# LPmini-Prototype_1_4b.net
KiCad netlist of a schematic drawn in EAGLE
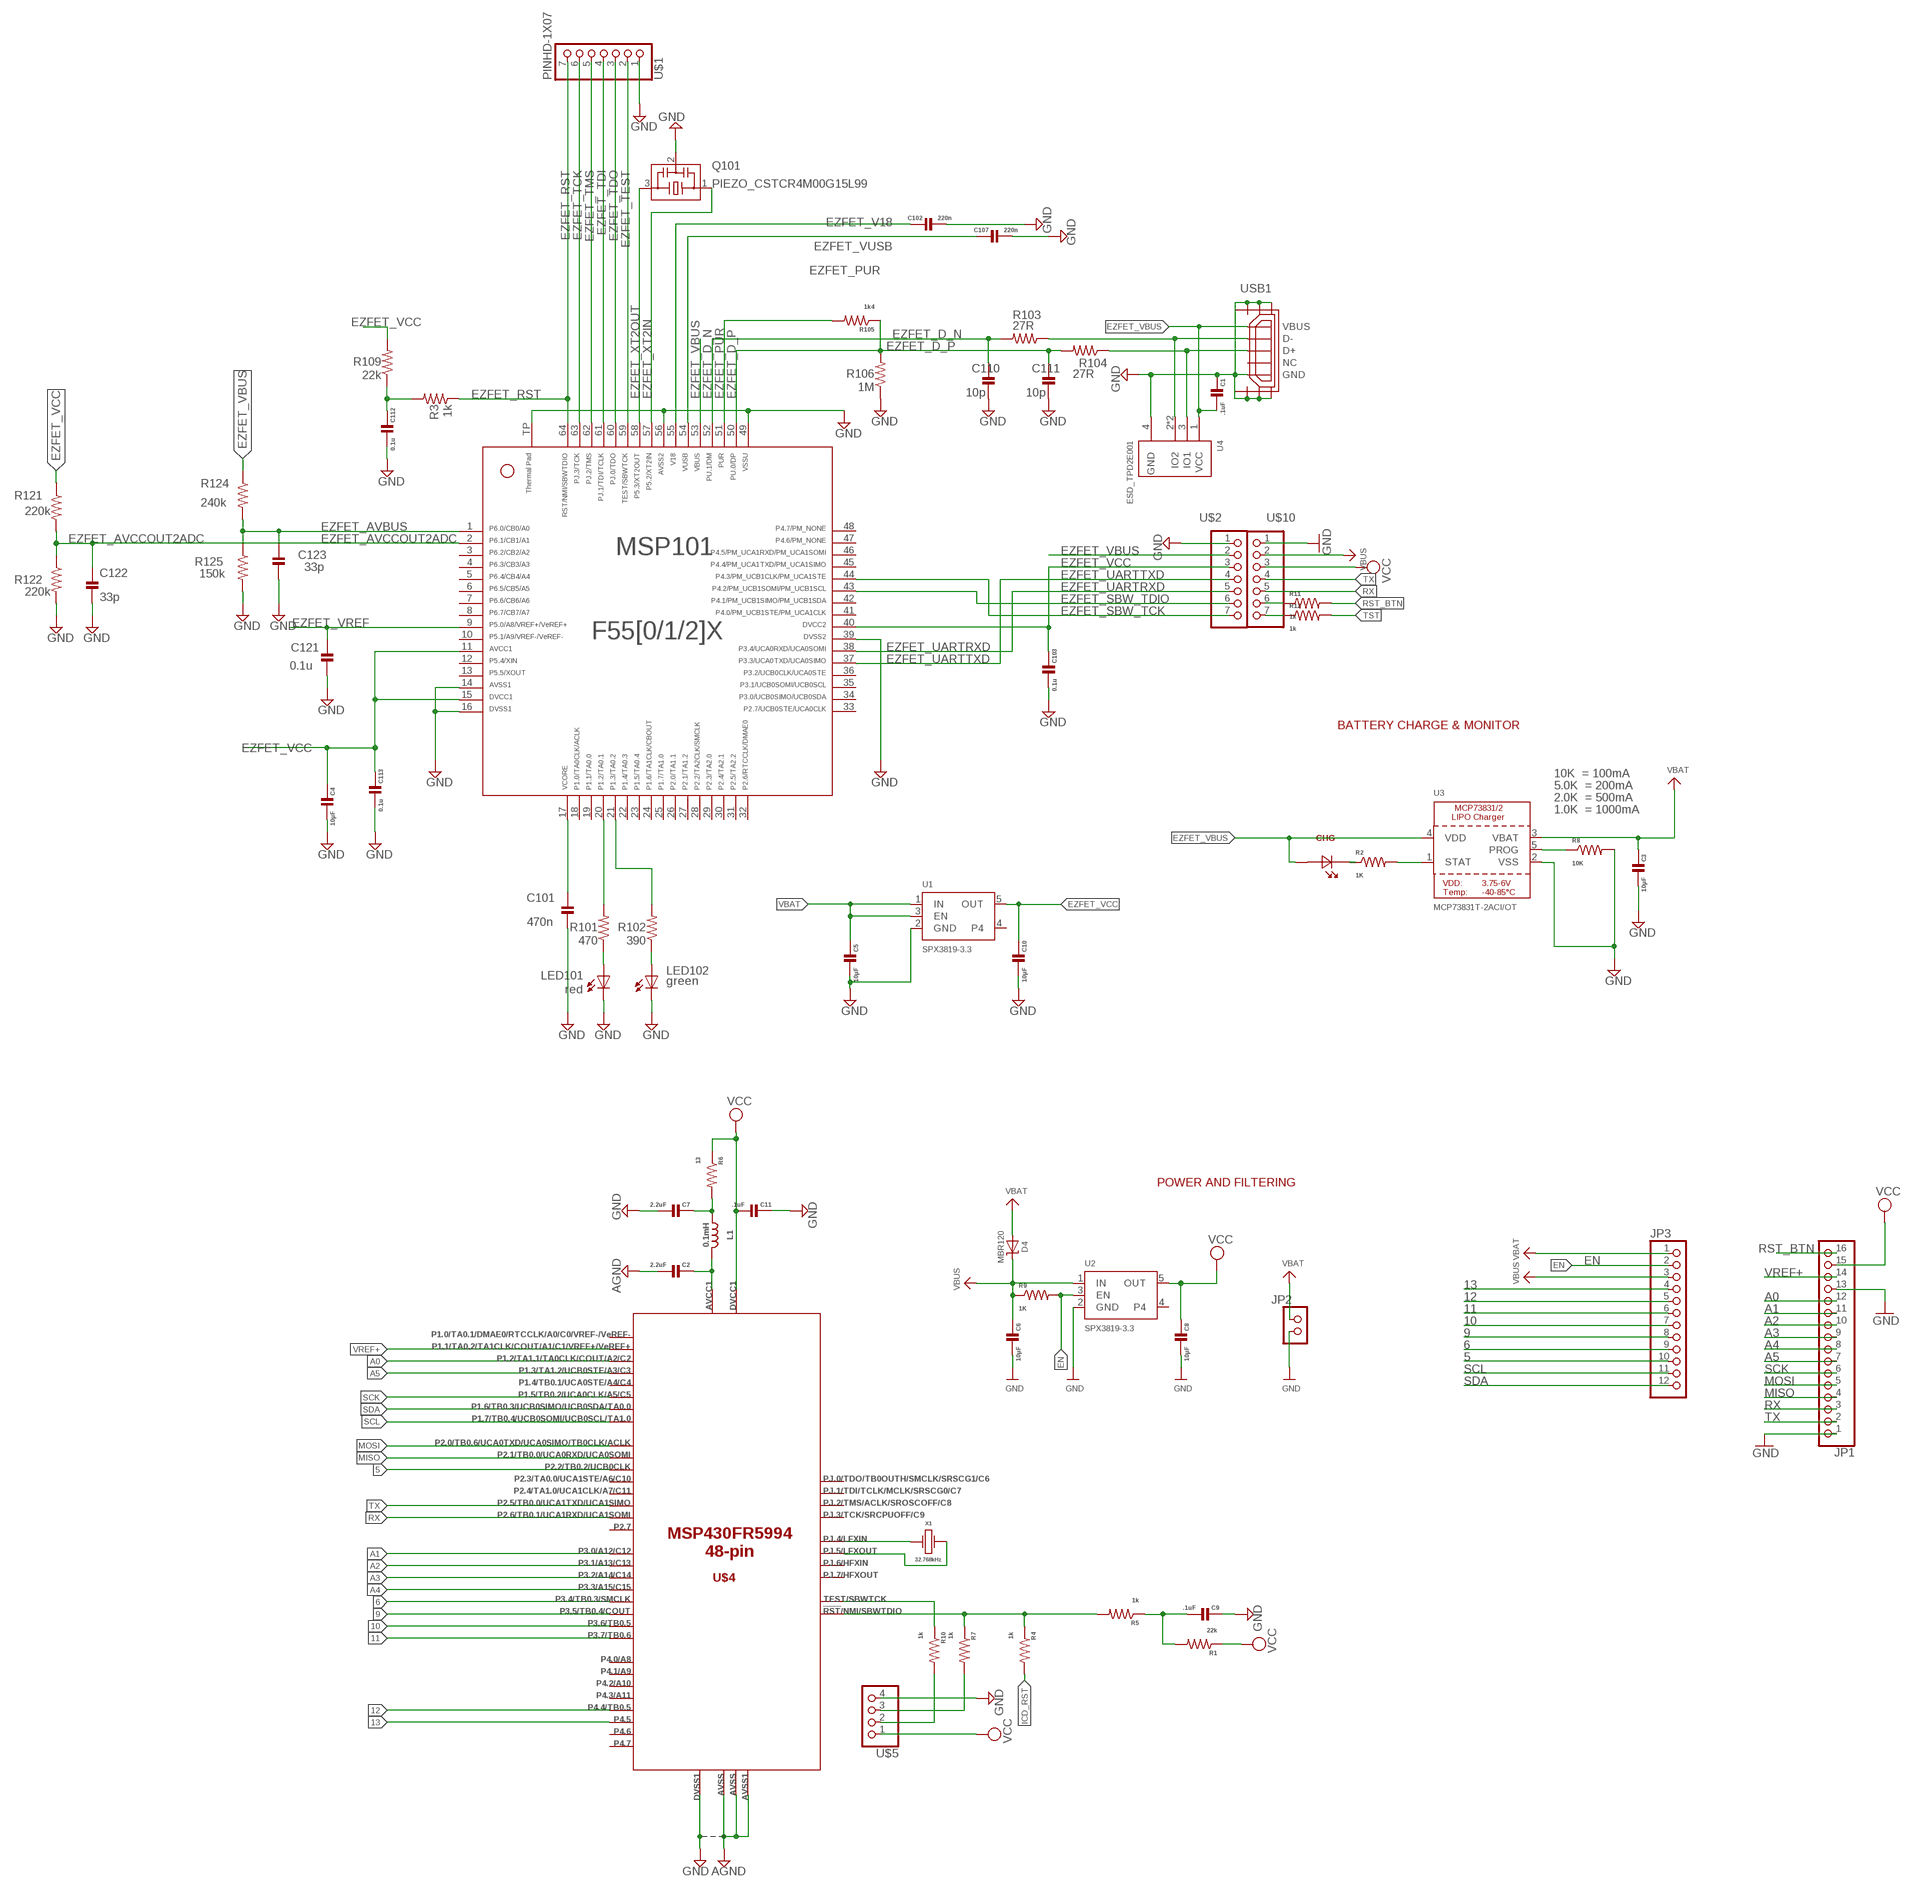
[diagram p0: schematic, sheet 1]

(export (version "E")
  (design (tool "Eeschema 10.0.6"))
  (components
    (comp (ref "C1")
      (value ".1uF")
      (footprint "eagle-import:C0402")
      (libsource (lib "eagle-import") (part "C-EUC0402"))
    )
    (comp (ref "C2")
      (value "2.2uF")
      (footprint "eagle-import:C0603")
      (libsource (lib "eagle-import") (part "C-EUC0603"))
    )
    (comp (ref "C3")
      (value "10µF")
      (footprint "eagle-import:C0603")
      (libsource (lib "eagle-import") (part "C-EUC0603"))
    )
    (comp (ref "C4")
      (value "10µF")
      (footprint "eagle-import:C0603")
      (libsource (lib "eagle-import") (part "C-EUC0603"))
    )
    (comp (ref "C5")
      (value "10µF")
      (footprint "eagle-import:C0603")
      (libsource (lib "eagle-import") (part "C-EUC0603"))
    )
    (comp (ref "C6")
      (value "10µF")
      (footprint "eagle-import:C0603")
      (libsource (lib "eagle-import") (part "C-EUC0603"))
    )
    (comp (ref "C7")
      (value "2.2uF")
      (footprint "eagle-import:C0603")
      (libsource (lib "eagle-import") (part "C-EUC0603"))
    )
    (comp (ref "C8")
      (value "10µF")
      (footprint "eagle-import:C0603")
      (libsource (lib "eagle-import") (part "C-EUC0603"))
    )
    (comp (ref "C9")
      (value ".1uF")
      (footprint "eagle-import:C0402")
      (libsource (lib "eagle-import") (part "C-EUC0402"))
    )
    (comp (ref "C10")
      (value "10µF")
      (footprint "eagle-import:C0603")
      (libsource (lib "eagle-import") (part "C-EUC0603"))
    )
    (comp (ref "C11")
      (value ".1uF")
      (footprint "eagle-import:C0402")
      (libsource (lib "eagle-import") (part "C-EUC0402"))
    )
    (comp (ref "C101")
      (value "470n")
      (footprint "eagle-import:C0402")
      (libsource (lib "eagle-import") (part "C-EUC0402"))
    )
    (comp (ref "C102")
      (value "220n")
      (footprint "eagle-import:C0402")
      (libsource (lib "eagle-import") (part "C-EUC0402"))
    )
    (comp (ref "C103")
      (value "0.1u")
      (footprint "eagle-import:C0402")
      (libsource (lib "eagle-import") (part "C-EUC0402"))
    )
    (comp (ref "C107")
      (value "220n")
      (footprint "eagle-import:C0402")
      (libsource (lib "eagle-import") (part "C-EUC0402"))
    )
    (comp (ref "C110")
      (value "10p")
      (footprint "eagle-import:C0402")
      (libsource (lib "eagle-import") (part "C-EUC0402"))
    )
    (comp (ref "C111")
      (value "10p")
      (footprint "eagle-import:C0402")
      (libsource (lib "eagle-import") (part "C-EUC0402"))
    )
    (comp (ref "C112")
      (value "0.1u")
      (footprint "eagle-import:C0402")
      (libsource (lib "eagle-import") (part "C-EUC0402"))
    )
    (comp (ref "C113")
      (value "0.1u")
      (footprint "eagle-import:C0402")
      (libsource (lib "eagle-import") (part "C-EUC0402"))
    )
    (comp (ref "C121")
      (value "0.1u")
      (footprint "eagle-import:C0402")
      (libsource (lib "eagle-import") (part "C-EUC0402"))
    )
    (comp (ref "C122")
      (value "33p")
      (footprint "eagle-import:C0402")
      (libsource (lib "eagle-import") (part "C-EUC0402"))
    )
    (comp (ref "C123")
      (value "33p")
      (footprint "eagle-import:C0402")
      (libsource (lib "eagle-import") (part "C-EUC0402"))
    )
    (comp (ref "CHG")
      (value "ORANGE")
      (footprint "eagle-import:LED_0603")
      (libsource (lib "eagle-import") (part "LED0603"))
    )
    (comp (ref "D4")
      (value "MBR120")
      (footprint "eagle-import:SOD-123")
      (libsource (lib "eagle-import") (part "DIODE-SCHOTTKYSOD-123"))
    )
    (comp (ref "JP1")
      (value "HEADER-1X16ROUND")
      (footprint "eagle-import:1X16_ROUND")
      (libsource (lib "eagle-import") (part "HEADER-1X16ROUND"))
    )
    (comp (ref "JP2")
      (value "0_JOSEPH_PINHD-1X2END")
      (footprint "eagle-import:0_JOSEPH_1X02-END")
      (libsource (lib "eagle-import") (part "0_JOSEPH_PINHD-1X2END"))
    )
    (comp (ref "JP3")
      (value "HEADER-1X12")
      (footprint "eagle-import:1X12_ROUND")
      (libsource (lib "eagle-import") (part "HEADER-1X12"))
    )
    (comp (ref "L1")
      (value "0.1mH")
      (footprint "eagle-import:RCL_R0805")
      (libsource (lib "eagle-import") (part "SMD_INDUCT0805"))
    )
    (comp (ref "LED101")
      (value "red")
      (footprint "eagle-import:CHIP-LED0603")
      (libsource (lib "eagle-import") (part "LEDCHIP-LED0603"))
    )
    (comp (ref "LED102")
      (value "green")
      (footprint "eagle-import:CHIP-LED0603")
      (libsource (lib "eagle-import") (part "LEDCHIP-LED0603"))
    )
    (comp (ref "MSP101")
      (value "MSP430F5528IRGC")
      (footprint "eagle-import:RGC64")
      (libsource (lib "eagle-import") (part "F55[0/1/2]X---RGC64"))
    )
    (comp (ref "Q101")
      (value "PIEZO_CSTCR4M00G15L99")
      (footprint "eagle-import:MURATA-FILTER_CSTCR")
      (fields (field (name "MPN") "CSTCR6M00G53-R0"))
      (libsource (lib "eagle-import") (part "MURATA-FILTER_CSTCR6M00G53Z"))
    )
    (comp (ref "R1")
      (value "22k")
      (footprint "eagle-import:R0402")
      (libsource (lib "eagle-import") (part "R-US_R0402"))
    )
    (comp (ref "R2")
      (value "1K")
      (footprint "eagle-import:R0402")
      (libsource (lib "eagle-import") (part "R-US_R0402"))
    )
    (comp (ref "R3")
      (value "1k")
      (footprint "eagle-import:R0402")
      (libsource (lib "eagle-import") (part "R-US_R0402"))
    )
    (comp (ref "R4")
      (value "1k")
      (footprint "eagle-import:R0402")
      (libsource (lib "eagle-import") (part "R-US_R0402"))
    )
    (comp (ref "R5")
      (value "1k")
      (footprint "eagle-import:R0402")
      (libsource (lib "eagle-import") (part "R-US_R0402"))
    )
    (comp (ref "R6")
      (value "13")
      (footprint "eagle-import:R0402")
      (libsource (lib "eagle-import") (part "R-US_R0402"))
    )
    (comp (ref "R7")
      (value "1k")
      (footprint "eagle-import:R0402")
      (libsource (lib "eagle-import") (part "R-US_R0402"))
    )
    (comp (ref "R8")
      (value "10K")
      (footprint "eagle-import:R0402")
      (libsource (lib "eagle-import") (part "R-US_R0402"))
    )
    (comp (ref "R9")
      (value "1K")
      (footprint "eagle-import:R0402")
      (libsource (lib "eagle-import") (part "R-US_R0402"))
    )
    (comp (ref "R10")
      (value "1k")
      (footprint "eagle-import:R0402")
      (libsource (lib "eagle-import") (part "R-US_R0402"))
    )
    (comp (ref "R11")
      (value "1k")
      (footprint "eagle-import:R0402")
      (libsource (lib "eagle-import") (part "R-US_R0402"))
    )
    (comp (ref "R12")
      (value "1k")
      (footprint "eagle-import:R0402")
      (libsource (lib "eagle-import") (part "R-US_R0402"))
    )
    (comp (ref "R101")
      (value "470")
      (footprint "eagle-import:R0402")
      (libsource (lib "eagle-import") (part "R-US_R0402"))
    )
    (comp (ref "R102")
      (value "390")
      (footprint "eagle-import:R0402")
      (libsource (lib "eagle-import") (part "R-US_R0402"))
    )
    (comp (ref "R103")
      (value "27R")
      (footprint "eagle-import:R0402")
      (libsource (lib "eagle-import") (part "R-US_R0402"))
    )
    (comp (ref "R104")
      (value "27R")
      (footprint "eagle-import:R0402")
      (libsource (lib "eagle-import") (part "R-US_R0402"))
    )
    (comp (ref "R105")
      (value "1k4")
      (footprint "eagle-import:R0402")
      (libsource (lib "eagle-import") (part "R-US_R0402"))
    )
    (comp (ref "R106")
      (value "1M")
      (footprint "eagle-import:R0402")
      (libsource (lib "eagle-import") (part "R-US_R0402"))
    )
    (comp (ref "R109")
      (value "22k")
      (footprint "eagle-import:R0402")
      (libsource (lib "eagle-import") (part "R-US_R0402"))
    )
    (comp (ref "R121")
      (value "220k")
      (footprint "eagle-import:R0402")
      (libsource (lib "eagle-import") (part "R-US_R0402"))
    )
    (comp (ref "R122")
      (value "220k")
      (footprint "eagle-import:R0402")
      (libsource (lib "eagle-import") (part "R-US_R0402"))
    )
    (comp (ref "R124")
      (value "240k")
      (footprint "eagle-import:R0402")
      (libsource (lib "eagle-import") (part "R-US_R0402"))
    )
    (comp (ref "R125")
      (value "150k")
      (footprint "eagle-import:R0402")
      (libsource (lib "eagle-import") (part "R-US_R0402"))
    )
    (comp (ref "U$1")
      (value "PINHD-1X07")
      (footprint "eagle-import:1X07")
      (libsource (lib "eagle-import") (part "PINHD-1X07"))
    )
    (comp (ref "U$2")
      (value "PINHD-1X07")
      (footprint "eagle-import:1X07")
      (libsource (lib "eagle-import") (part "PINHD-1X07"))
    )
    (comp (ref "U$4")
      (value "MSP430FR5994-48PIN")
      (footprint "eagle-import:48QFN")
      (libsource (lib "eagle-import") (part "MSP430FR5994-48PIN"))
    )
    (comp (ref "U$5")
      (value "PINHD_1X4")
      (footprint "eagle-import:1X04")
      (libsource (lib "eagle-import") (part "PINHD_1X4"))
    )
    (comp (ref "U$10")
      (value "PINHD-1X07")
      (footprint "eagle-import:1X07")
      (libsource (lib "eagle-import") (part "PINHD-1X07"))
    )
    (comp (ref "U1")
      (value "SPX3819-3.3")
      (footprint "eagle-import:SOT23-5")
      (libsource (lib "eagle-import") (part "VREG_SOT23-5"))
    )
    (comp (ref "U2")
      (value "SPX3819-3.3")
      (footprint "eagle-import:SOT23-5")
      (libsource (lib "eagle-import") (part "VREG_SOT23-5"))
    )
    (comp (ref "U3")
      (value "MCP73831T-2ACI/OT")
      (footprint "eagle-import:SOT23-5")
      (libsource (lib "eagle-import") (part "MCP73831/2"))
    )
    (comp (ref "U4")
      (value "ESD_TPD2E001")
      (footprint "eagle-import:PROJECT7264_TPD2E001-DRL")
      (libsource (lib "eagle-import") (part "ESD_TPD2E001"))
    )
    (comp (ref "USB1")
      (value "USB_CON-UPDATE_USB_MICRO_FLIPPED")
      (footprint "eagle-import:USB_CON-UPDATE_HIROSE-ZX62R-B-5P")
      (libsource (lib "eagle-import") (part "USB_CON-UPDATE_USB_MICRO_FLIPPED"))
    )
    (comp (ref "X1")
      (value "32.768kHz")
      (footprint "eagle-import:CRYSTAL_ABS05")
      (libsource (lib "eagle-import") (part "CRYSTALABS-05"))
    )
  )
  (nets
    (net (code "1") (name "/EZFET_AVBUS") (class "Default")
      (node (ref "C123") (pin "2") (pinfunction "2_2") (pintype "passive"))
      (node (ref "MSP101") (pin "1") (pinfunction "1_1") (pintype "bidirectional"))
      (node (ref "R124") (pin "2") (pinfunction "2_2") (pintype "passive"))
      (node (ref "R125") (pin "1") (pinfunction "1_1") (pintype "passive"))
    )
    (net (code "2") (name "/EZFET_AVCCOUT2ADC") (class "Default")
      (node (ref "C122") (pin "2") (pinfunction "2_2") (pintype "passive"))
      (node (ref "MSP101") (pin "2") (pinfunction "2_2") (pintype "bidirectional"))
      (node (ref "R121") (pin "2") (pinfunction "2_2") (pintype "passive"))
      (node (ref "R122") (pin "1") (pinfunction "1_1") (pintype "passive"))
    )
    (net (code "3") (name "/EZFET_D_N") (class "Default")
      (node (ref "C110") (pin "1") (pinfunction "1_1") (pintype "passive"))
      (node (ref "MSP101") (pin "52") (pinfunction "52_52") (pintype "bidirectional"))
      (node (ref "R103") (pin "2") (pinfunction "2_2") (pintype "passive"))
    )
    (net (code "4") (name "/EZFET_D_P") (class "Default")
      (node (ref "C111") (pin "1") (pinfunction "1_1") (pintype "passive"))
      (node (ref "MSP101") (pin "50") (pinfunction "50_50") (pintype "bidirectional"))
      (node (ref "R104") (pin "2") (pinfunction "2_2") (pintype "passive"))
      (node (ref "R105") (pin "1") (pinfunction "1_1") (pintype "passive"))
      (node (ref "R106") (pin "2") (pinfunction "2_2") (pintype "passive"))
    )
    (net (code "5") (name "/EZFET_PUR") (class "Default")
      (node (ref "MSP101") (pin "51") (pinfunction "51_51") (pintype "bidirectional"))
      (node (ref "R105") (pin "2") (pinfunction "2_2") (pintype "passive"))
    )
    (net (code "6") (name "/EZFET_RST") (class "Default")
      (node (ref "MSP101") (pin "64") (pinfunction "64_64") (pintype "bidirectional"))
      (node (ref "R3") (pin "1") (pinfunction "1_1") (pintype "passive"))
      (node (ref "U$1") (pin "7") (pinfunction "7_7") (pintype "passive"))
    )
    (net (code "7") (name "/EZFET_SBW_TCK") (class "Default")
      (node (ref "MSP101") (pin "44") (pinfunction "44_44") (pintype "bidirectional"))
      (node (ref "U$2") (pin "7") (pinfunction "7_7") (pintype "passive"))
    )
    (net (code "8") (name "/EZFET_SBW_TDIO") (class "Default")
      (node (ref "MSP101") (pin "43") (pinfunction "43_43") (pintype "bidirectional"))
      (node (ref "U$2") (pin "6") (pinfunction "6_6") (pintype "passive"))
    )
    (net (code "9") (name "/EZFET_TCK") (class "Default")
      (node (ref "MSP101") (pin "63") (pinfunction "63_63") (pintype "bidirectional"))
      (node (ref "U$1") (pin "6") (pinfunction "6_6") (pintype "passive"))
    )
    (net (code "10") (name "/EZFET_TDI") (class "Default")
      (node (ref "MSP101") (pin "61") (pinfunction "61_61") (pintype "bidirectional"))
      (node (ref "U$1") (pin "4") (pinfunction "4_4") (pintype "passive"))
    )
    (net (code "11") (name "/EZFET_TDO") (class "Default")
      (node (ref "MSP101") (pin "60") (pinfunction "60_60") (pintype "bidirectional"))
      (node (ref "U$1") (pin "3") (pinfunction "3_3") (pintype "passive"))
    )
    (net (code "12") (name "/EZFET_TEST") (class "Default")
      (node (ref "MSP101") (pin "59") (pinfunction "59_59") (pintype "input"))
      (node (ref "U$1") (pin "2") (pinfunction "2_2") (pintype "passive"))
    )
    (net (code "13") (name "/EZFET_TMS") (class "Default")
      (node (ref "MSP101") (pin "62") (pinfunction "62_62") (pintype "bidirectional"))
      (node (ref "U$1") (pin "5") (pinfunction "5_5") (pintype "passive"))
    )
    (net (code "14") (name "/EZFET_UARTRXD") (class "Default")
      (node (ref "MSP101") (pin "38") (pinfunction "38_38") (pintype "bidirectional"))
      (node (ref "U$2") (pin "5") (pinfunction "5_5") (pintype "passive"))
    )
    (net (code "15") (name "/EZFET_UARTTXD") (class "Default")
      (node (ref "MSP101") (pin "37") (pinfunction "37_37") (pintype "bidirectional"))
      (node (ref "U$2") (pin "4") (pinfunction "4_4") (pintype "passive"))
    )
    (net (code "16") (name "/EZFET_V18") (class "Default")
      (node (ref "C102") (pin "1") (pinfunction "1_1") (pintype "passive"))
      (node (ref "MSP101") (pin "55") (pinfunction "55_55") (pintype "power_in"))
    )
    (net (code "17") (name "/EZFET_VREF") (class "Default")
      (node (ref "C121") (pin "1") (pinfunction "1_1") (pintype "passive"))
      (node (ref "MSP101") (pin "9") (pinfunction "9_9") (pintype "bidirectional"))
    )
    (net (code "18") (name "/EZFET_VUSB") (class "Default")
      (node (ref "C107") (pin "1") (pinfunction "1_1") (pintype "passive"))
      (node (ref "MSP101") (pin "54") (pinfunction "54_54") (pintype "power_in"))
    )
    (net (code "19") (name "/EZFET_XT2IN") (class "Default")
      (node (ref "MSP101") (pin "57") (pinfunction "57_57") (pintype "bidirectional"))
      (node (ref "Q101") (pin "1") (pinfunction "1_1") (pintype "passive"))
    )
    (net (code "20") (name "/EZFET_XT2OUT") (class "Default")
      (node (ref "MSP101") (pin "58") (pinfunction "58_58") (pintype "bidirectional"))
      (node (ref "Q101") (pin "3") (pinfunction "3_3") (pintype "passive"))
    )
    (net (code "21") (name "5") (class "Default")
      (node (ref "JP3") (pin "10") (pinfunction "10_10") (pintype "passive"))
      (node (ref "U$4") (pin "26") (pinfunction "26_26") (pintype "bidirectional"))
    )
    (net (code "22") (name "6") (class "Default")
      (node (ref "JP3") (pin "9") (pinfunction "9_9") (pintype "passive"))
      (node (ref "U$4") (pin "27") (pinfunction "27_27") (pintype "bidirectional"))
    )
    (net (code "23") (name "9") (class "Default")
      (node (ref "JP3") (pin "8") (pinfunction "8_8") (pintype "passive"))
      (node (ref "U$4") (pin "28") (pinfunction "28_28") (pintype "bidirectional"))
    )
    (net (code "24") (name "10") (class "Default")
      (node (ref "JP3") (pin "7") (pinfunction "7_7") (pintype "passive"))
      (node (ref "U$4") (pin "29") (pinfunction "29_29") (pintype "bidirectional"))
    )
    (net (code "25") (name "11") (class "Default")
      (node (ref "JP3") (pin "6") (pinfunction "6_6") (pintype "passive"))
      (node (ref "U$4") (pin "30") (pinfunction "30_30") (pintype "bidirectional"))
    )
    (net (code "26") (name "12") (class "Default")
      (node (ref "JP3") (pin "5") (pinfunction "5_5") (pintype "passive"))
      (node (ref "U$4") (pin "33") (pinfunction "33_33") (pintype "bidirectional"))
    )
    (net (code "27") (name "13") (class "Default")
      (node (ref "JP3") (pin "4") (pinfunction "4_4") (pintype "passive"))
      (node (ref "U$4") (pin "34") (pinfunction "34_34") (pintype "bidirectional"))
    )
    (net (code "28") (name "A0") (class "Default")
      (node (ref "JP1") (pin "12") (pinfunction "12_12") (pintype "passive"))
      (node (ref "U$4") (pin "3") (pinfunction "3_3") (pintype "bidirectional"))
    )
    (net (code "29") (name "A1") (class "Default")
      (node (ref "JP1") (pin "11") (pinfunction "11_11") (pintype "passive"))
      (node (ref "U$4") (pin "4") (pinfunction "4_4") (pintype "bidirectional"))
    )
    (net (code "30") (name "A2") (class "Default")
      (node (ref "JP1") (pin "10") (pinfunction "10_10") (pintype "passive"))
      (node (ref "U$4") (pin "5") (pinfunction "5_5") (pintype "bidirectional"))
    )
    (net (code "31") (name "A3") (class "Default")
      (node (ref "JP1") (pin "9") (pinfunction "9_9") (pintype "passive"))
      (node (ref "U$4") (pin "6") (pinfunction "6_6") (pintype "bidirectional"))
    )
    (net (code "32") (name "A4") (class "Default")
      (node (ref "JP1") (pin "8") (pinfunction "8_8") (pintype "passive"))
      (node (ref "U$4") (pin "7") (pinfunction "7_7") (pintype "bidirectional"))
    )
    (net (code "33") (name "A5") (class "Default")
      (node (ref "JP1") (pin "7") (pinfunction "7_7") (pintype "passive"))
      (node (ref "U$4") (pin "9") (pinfunction "9_9") (pintype "bidirectional"))
    )
    (net (code "34") (name "AGND") (class "Default")
      (node (ref "C2") (pin "2") (pinfunction "2_2") (pintype "passive"))
      (node (ref "U$4") (pin "41") (pinfunction "41_41") (pintype "bidirectional"))
      (node (ref "U$4") (pin "44") (pinfunction "44_44") (pintype "bidirectional"))
      (node (ref "U$4") (pin "47") (pinfunction "47_47") (pintype "bidirectional"))
    )
    (net (code "35") (name "EN") (class "Default")
      (node (ref "JP3") (pin "2") (pinfunction "2_2") (pintype "passive"))
      (node (ref "R9") (pin "2") (pinfunction "2_2") (pintype "passive"))
      (node (ref "U2") (pin "3") (pinfunction "EN_3") (pintype "input"))
    )
    (net (code "36") (name "EZFET_VBUS") (class "Default")
      (node (ref "C1") (pin "2") (pinfunction "2_2") (pintype "passive"))
      (node (ref "CHG") (pin "A") (pinfunction "A_A") (pintype "bidirectional"))
      (node (ref "MSP101") (pin "53") (pinfunction "53_53") (pintype "power_in"))
      (node (ref "R124") (pin "1") (pinfunction "1_1") (pintype "passive"))
      (node (ref "U$2") (pin "2") (pinfunction "2_2") (pintype "passive"))
      (node (ref "U3") (pin "4") (pinfunction "VDD_4") (pintype "power_in"))
      (node (ref "U4") (pin "1") (pinfunction "VCC_1") (pintype "power_in"))
      (node (ref "USB1") (pin "VBUS") (pinfunction "VBUS_VBUS") (pintype "input"))
    )
    (net (code "37") (name "EZFET_VCC") (class "Default")
      (node (ref "C10") (pin "1") (pinfunction "1_1") (pintype "passive"))
      (node (ref "C103") (pin "1") (pinfunction "1_1") (pintype "passive"))
      (node (ref "C113") (pin "1") (pinfunction "1_1") (pintype "passive"))
      (node (ref "C4") (pin "1") (pinfunction "1_1") (pintype "passive"))
      (node (ref "MSP101") (pin "11") (pinfunction "11_11") (pintype "power_in"))
      (node (ref "MSP101") (pin "15") (pinfunction "15_15") (pintype "power_in"))
      (node (ref "MSP101") (pin "40") (pinfunction "40_40") (pintype "power_in"))
      (node (ref "R109") (pin "2") (pinfunction "2_2") (pintype "passive"))
      (node (ref "R121") (pin "1") (pinfunction "1_1") (pintype "passive"))
      (node (ref "U$2") (pin "3") (pinfunction "3_3") (pintype "passive"))
      (node (ref "U1") (pin "5") (pinfunction "OUT_5") (pintype "power_in"))
    )
    (net (code "38") (name "GND") (class "Default")
      (node (ref "C1") (pin "1") (pinfunction "1_1") (pintype "passive"))
      (node (ref "C10") (pin "2") (pinfunction "2_2") (pintype "passive"))
      (node (ref "C101") (pin "2") (pinfunction "2_2") (pintype "passive"))
      (node (ref "C102") (pin "2") (pinfunction "2_2") (pintype "passive"))
      (node (ref "C103") (pin "2") (pinfunction "2_2") (pintype "passive"))
      (node (ref "C107") (pin "2") (pinfunction "2_2") (pintype "passive"))
      (node (ref "C11") (pin "1") (pinfunction "1_1") (pintype "passive"))
      (node (ref "C110") (pin "2") (pinfunction "2_2") (pintype "passive"))
      (node (ref "C111") (pin "2") (pinfunction "2_2") (pintype "passive"))
      (node (ref "C112") (pin "2") (pinfunction "2_2") (pintype "passive"))
      (node (ref "C113") (pin "2") (pinfunction "2_2") (pintype "passive"))
      (node (ref "C121") (pin "2") (pinfunction "2_2") (pintype "passive"))
      (node (ref "C122") (pin "1") (pinfunction "1_1") (pintype "passive"))
      (node (ref "C123") (pin "1") (pinfunction "1_1") (pintype "passive"))
      (node (ref "C3") (pin "2") (pinfunction "2_2") (pintype "passive"))
      (node (ref "C4") (pin "2") (pinfunction "2_2") (pintype "passive"))
      (node (ref "C5") (pin "2") (pinfunction "2_2") (pintype "passive"))
      (node (ref "C6") (pin "2") (pinfunction "2_2") (pintype "passive"))
      (node (ref "C7") (pin "2") (pinfunction "2_2") (pintype "passive"))
      (node (ref "C8") (pin "2") (pinfunction "2_2") (pintype "passive"))
      (node (ref "C9") (pin "1") (pinfunction "1_1") (pintype "passive"))
      (node (ref "JP1") (pin "1") (pinfunction "1_1") (pintype "passive"))
      (node (ref "JP1") (pin "13") (pinfunction "13_13") (pintype "passive"))
      (node (ref "JP2") (pin "2") (pinfunction "2_2") (pintype "passive"))
      (node (ref "LED101") (pin "C") (pinfunction "C_C") (pintype "passive"))
      (node (ref "LED102") (pin "C") (pinfunction "C_C") (pintype "passive"))
      (node (ref "MSP101") (pin "14") (pinfunction "14_14") (pintype "power_in"))
      (node (ref "MSP101") (pin "16") (pinfunction "16_16") (pintype "power_in"))
      (node (ref "MSP101") (pin "39") (pinfunction "39_39") (pintype "power_in"))
      (node (ref "MSP101") (pin "49") (pinfunction "49_49") (pintype "power_in"))
      (node (ref "MSP101") (pin "56") (pinfunction "56_56") (pintype "power_in"))
      (node (ref "MSP101") (pin "TP") (pinfunction "TP_TP") (pintype "power_in"))
      (node (ref "Q101") (pin "2") (pinfunction "2_2") (pintype "passive"))
      (node (ref "R106") (pin "1") (pinfunction "1_1") (pintype "passive"))
      (node (ref "R122") (pin "2") (pinfunction "2_2") (pintype "passive"))
      (node (ref "R125") (pin "2") (pinfunction "2_2") (pintype "passive"))
      (node (ref "R8") (pin "2") (pinfunction "2_2") (pintype "passive"))
      (node (ref "U$1") (pin "1") (pinfunction "1_1") (pintype "passive"))
      (node (ref "U$10") (pin "1") (pinfunction "1_1") (pintype "passive"))
      (node (ref "U$2") (pin "1") (pinfunction "1_1") (pintype "passive"))
      (node (ref "U$4") (pin "36") (pinfunction "36_36") (pintype "bidirectional"))
      (node (ref "U$4") (pin "TAB") (pinfunction "36_TAB") (pintype "bidirectional"))
      (node (ref "U$5") (pin "4") (pinfunction "4_4") (pintype "passive"))
      (node (ref "U1") (pin "2") (pinfunction "GND_2") (pintype "power_in"))
      (node (ref "U2") (pin "2") (pinfunction "GND_2") (pintype "power_in"))
      (node (ref "U3") (pin "2") (pinfunction "VSS_2") (pintype "power_in"))
      (node (ref "U4") (pin "4") (pinfunction "GND_4") (pintype "power_in"))
      (node (ref "USB1") (pin "GND") (pinfunction "GND_GND") (pintype "input"))
      (node (ref "USB1") (pin "SHIELD1") (pinfunction "SHIELD1_SHIELD1") (pintype "bidirectional"))
      (node (ref "USB1") (pin "SHIELD2") (pinfunction "SHIELD2_SHIELD2") (pintype "bidirectional"))
      (node (ref "USB1") (pin "SHIELD3") (pinfunction "SHIELD3_SHIELD3") (pintype "bidirectional"))
      (node (ref "USB1") (pin "SHIELD4") (pinfunction "SHIELD4_SHIELD4") (pintype "bidirectional"))
      (node (ref "USB1") (pin "SHIELD5") (pinfunction "SHIELD5_SHIELD5") (pintype "bidirectional"))
      (node (ref "USB1") (pin "SHIELD6") (pinfunction "SHIELD6_SHIELD6") (pintype "bidirectional"))
    )
    (net (code "39") (name "ICD_RST") (class "Default")
      (node (ref "R4") (pin "2") (pinfunction "2_2") (pintype "passive"))
    )
    (net (code "40") (name "MISO") (class "Default")
      (node (ref "JP1") (pin "4") (pinfunction "4_4") (pintype "passive"))
      (node (ref "U$4") (pin "25") (pinfunction "25_25") (pintype "bidirectional"))
    )
    (net (code "41") (name "MOSI") (class "Default")
      (node (ref "JP1") (pin "5") (pinfunction "5_5") (pintype "passive"))
      (node (ref "U$4") (pin "24") (pinfunction "24_24") (pintype "bidirectional"))
    )
    (net (code "42") (name "Net-(C9-Pad2)") (class "Default")
      (node (ref "C9") (pin "2") (pinfunction "2_2") (pintype "passive"))
      (node (ref "R1") (pin "2") (pinfunction "2_2") (pintype "passive"))
      (node (ref "R5") (pin "1") (pinfunction "1_1") (pintype "passive"))
    )
    (net (code "43") (name "Net-(C101-Pad1)") (class "Default")
      (node (ref "C101") (pin "1") (pinfunction "1_1") (pintype "passive"))
      (node (ref "MSP101") (pin "17") (pinfunction "17_17") (pintype "power_in"))
    )
    (net (code "44") (name "Net-(C112-Pad1)") (class "Default")
      (node (ref "C112") (pin "1") (pinfunction "1_1") (pintype "passive"))
      (node (ref "R109") (pin "1") (pinfunction "1_1") (pintype "passive"))
      (node (ref "R3") (pin "2") (pinfunction "2_2") (pintype "passive"))
    )
    (net (code "45") (name "Net-(CHG-C)") (class "Default")
      (node (ref "CHG") (pin "K") (pinfunction "C_K") (pintype "bidirectional"))
      (node (ref "R2") (pin "1") (pinfunction "1_1") (pintype "passive"))
    )
    (net (code "46") (name "Net-(L1-P$1)") (class "Default")
      (node (ref "C2") (pin "1") (pinfunction "1_1") (pintype "passive"))
      (node (ref "L1") (pin "1") (pinfunction "P$1_1") (pintype "bidirectional"))
      (node (ref "U$4") (pin "48") (pinfunction "48_48") (pintype "bidirectional"))
    )
    (net (code "47") (name "Net-(L1-P$2)") (class "Default")
      (node (ref "C7") (pin "1") (pinfunction "1_1") (pintype "passive"))
      (node (ref "L1") (pin "2") (pinfunction "P$2_2") (pintype "bidirectional"))
      (node (ref "R6") (pin "2") (pinfunction "2_2") (pintype "passive"))
    )
    (net (code "48") (name "Net-(LED101-PadA)") (class "Default")
      (node (ref "LED101") (pin "A") (pinfunction "A_A") (pintype "passive"))
      (node (ref "R101") (pin "1") (pinfunction "1_1") (pintype "passive"))
    )
    (net (code "49") (name "Net-(LED102-PadA)") (class "Default")
      (node (ref "LED102") (pin "A") (pinfunction "A_A") (pintype "passive"))
      (node (ref "R102") (pin "1") (pinfunction "1_1") (pintype "passive"))
    )
    (net (code "50") (name "Net-(MSP101-Pad20)") (class "Default")
      (node (ref "MSP101") (pin "20") (pinfunction "20_20") (pintype "bidirectional"))
      (node (ref "R101") (pin "2") (pinfunction "2_2") (pintype "passive"))
    )
    (net (code "51") (name "Net-(MSP101-Pad21)") (class "Default")
      (node (ref "MSP101") (pin "21") (pinfunction "21_21") (pintype "bidirectional"))
      (node (ref "R102") (pin "2") (pinfunction "2_2") (pintype "passive"))
    )
    (net (code "52") (name "Net-(R4-Pad1)") (class "Default")
      (node (ref "R4") (pin "1") (pinfunction "1_1") (pintype "passive"))
      (node (ref "R5") (pin "2") (pinfunction "2_2") (pintype "passive"))
      (node (ref "R7") (pin "1") (pinfunction "1_1") (pintype "passive"))
      (node (ref "U$4") (pin "23") (pinfunction "23_23") (pintype "bidirectional"))
    )
    (net (code "53") (name "Net-(R10-Pad1)") (class "Default")
      (node (ref "R10") (pin "1") (pinfunction "1_1") (pintype "passive"))
      (node (ref "U$4") (pin "22") (pinfunction "22_22") (pintype "bidirectional"))
    )
    (net (code "54") (name "Net-(R11-Pad1)") (class "Default")
      (node (ref "R11") (pin "1") (pinfunction "1_1") (pintype "passive"))
      (node (ref "U$10") (pin "6") (pinfunction "6_6") (pintype "passive"))
    )
    (net (code "55") (name "Net-(R12-Pad1)") (class "Default")
      (node (ref "R12") (pin "1") (pinfunction "1_1") (pintype "passive"))
      (node (ref "U$10") (pin "7") (pinfunction "7_7") (pintype "passive"))
    )
    (net (code "56") (name "Net-(R103-Pad1)") (class "Default")
      (node (ref "R103") (pin "1") (pinfunction "1_1") (pintype "passive"))
      (node (ref "U4") (pin "2") (pinfunction "IO2_2") (pintype "bidirectional"))
      (node (ref "U4") (pin "5") (pinfunction "IO2_5") (pintype "bidirectional"))
      (node (ref "USB1") (pin "D-") (pinfunction "D-_D-") (pintype "input"))
    )
    (net (code "57") (name "Net-(U$4-Pad45)") (class "Default")
      (node (ref "U$4") (pin "45") (pinfunction "45_45") (pintype "bidirectional"))
      (node (ref "X1") (pin "P$1") (pinfunction "P$1_P$1") (pintype "bidirectional"))
    )
    (net (code "58") (name "Net-(U$4-Pad46)") (class "Default")
      (node (ref "U$4") (pin "46") (pinfunction "46_46") (pintype "bidirectional"))
      (node (ref "X1") (pin "P$2") (pinfunction "P$2_P$2") (pintype "bidirectional"))
    )
    (net (code "59") (name "Net-(U3-PROG)") (class "Default")
      (node (ref "R8") (pin "1") (pinfunction "1_1") (pintype "passive"))
      (node (ref "U3") (pin "5") (pinfunction "PROG_5") (pintype "input"))
    )
    (net (code "60") (name "Net-(U3-STAT)") (class "Default")
      (node (ref "R2") (pin "2") (pinfunction "2_2") (pintype "passive"))
      (node (ref "U3") (pin "1") (pinfunction "STAT_1") (pintype "output"))
    )
    (net (code "61") (name "Net-(U4-IO1)") (class "Default")
      (node (ref "R104") (pin "1") (pinfunction "1_1") (pintype "passive"))
      (node (ref "U4") (pin "3") (pinfunction "IO1_3") (pintype "bidirectional"))
      (node (ref "USB1") (pin "D+") (pinfunction "D+_D+") (pintype "input"))
    )
    (net (code "62") (name "RST_BTN") (class "Default")
      (node (ref "JP1") (pin "16") (pinfunction "16_16") (pintype "passive"))
      (node (ref "R11") (pin "2") (pinfunction "2_2") (pintype "passive"))
      (node (ref "R7") (pin "2") (pinfunction "2_2") (pintype "passive"))
      (node (ref "U$5") (pin "3") (pinfunction "3_3") (pintype "passive"))
    )
    (net (code "63") (name "RX") (class "Default")
      (node (ref "JP1") (pin "3") (pinfunction "3_3") (pintype "passive"))
      (node (ref "U$10") (pin "5") (pinfunction "5_5") (pintype "passive"))
      (node (ref "U$4") (pin "21") (pinfunction "21_21") (pintype "bidirectional"))
    )
    (net (code "64") (name "SCK") (class "Default")
      (node (ref "JP1") (pin "6") (pinfunction "6_6") (pintype "passive"))
      (node (ref "U$4") (pin "11") (pinfunction "11_11") (pintype "bidirectional"))
    )
    (net (code "65") (name "SCL") (class "Default")
      (node (ref "JP3") (pin "11") (pinfunction "11_11") (pintype "passive"))
      (node (ref "U$4") (pin "32") (pinfunction "32_32") (pintype "bidirectional"))
    )
    (net (code "66") (name "SDA") (class "Default")
      (node (ref "JP3") (pin "12") (pinfunction "12_12") (pintype "passive"))
      (node (ref "U$4") (pin "31") (pinfunction "31_31") (pintype "bidirectional"))
    )
    (net (code "67") (name "TST") (class "Default")
      (node (ref "R10") (pin "2") (pinfunction "2_2") (pintype "passive"))
      (node (ref "R12") (pin "2") (pinfunction "2_2") (pintype "passive"))
      (node (ref "U$5") (pin "2") (pinfunction "2_2") (pintype "passive"))
    )
    (net (code "68") (name "TX") (class "Default")
      (node (ref "JP1") (pin "2") (pinfunction "2_2") (pintype "passive"))
      (node (ref "U$10") (pin "4") (pinfunction "4_4") (pintype "passive"))
      (node (ref "U$4") (pin "20") (pinfunction "20_20") (pintype "bidirectional"))
    )
    (net (code "69") (name "VBAT") (class "Default")
      (node (ref "C3") (pin "1") (pinfunction "1_1") (pintype "passive"))
      (node (ref "C5") (pin "1") (pinfunction "1_1") (pintype "passive"))
      (node (ref "D4") (pin "A") (pinfunction "A_A") (pintype "passive"))
      (node (ref "JP2") (pin "1") (pinfunction "1_1") (pintype "passive"))
      (node (ref "JP3") (pin "1") (pinfunction "1_1") (pintype "passive"))
      (node (ref "U1") (pin "1") (pinfunction "IN_1") (pintype "power_in"))
      (node (ref "U1") (pin "3") (pinfunction "EN_3") (pintype "input"))
      (node (ref "U3") (pin "3") (pinfunction "VBAT_3") (pintype "power_in"))
    )
    (net (code "70") (name "VBUS") (class "Default")
      (node (ref "C6") (pin "1") (pinfunction "1_1") (pintype "passive"))
      (node (ref "D4") (pin "C") (pinfunction "C_C") (pintype "passive"))
      (node (ref "JP3") (pin "3") (pinfunction "3_3") (pintype "passive"))
      (node (ref "R9") (pin "1") (pinfunction "1_1") (pintype "passive"))
      (node (ref "U$10") (pin "2") (pinfunction "2_2") (pintype "passive"))
      (node (ref "U2") (pin "1") (pinfunction "IN_1") (pintype "power_in"))
    )
    (net (code "71") (name "VCC") (class "Default")
      (node (ref "C11") (pin "2") (pinfunction "2_2") (pintype "passive"))
      (node (ref "C8") (pin "1") (pinfunction "1_1") (pintype "passive"))
      (node (ref "JP1") (pin "15") (pinfunction "15_15") (pintype "passive"))
      (node (ref "R1") (pin "1") (pinfunction "1_1") (pintype "passive"))
      (node (ref "R6") (pin "1") (pinfunction "1_1") (pintype "passive"))
      (node (ref "U$10") (pin "3") (pinfunction "3_3") (pintype "passive"))
      (node (ref "U$4") (pin "37") (pinfunction "37_37") (pintype "bidirectional"))
      (node (ref "U$5") (pin "1") (pinfunction "1_1") (pintype "passive"))
      (node (ref "U2") (pin "5") (pinfunction "OUT_5") (pintype "power_in"))
    )
    (net (code "72") (name "VREF+") (class "Default")
      (node (ref "JP1") (pin "14") (pinfunction "14_14") (pintype "passive"))
      (node (ref "U$4") (pin "2") (pinfunction "2_2") (pintype "bidirectional"))
    )
    (net (code "73") (name "unconnected-(MSP101-Pad3)") (class "Default")
      (node (ref "MSP101") (pin "3") (pinfunction "3_3") (pintype "bidirectional"))
    )
    (net (code "74") (name "unconnected-(MSP101-Pad4)") (class "Default")
      (node (ref "MSP101") (pin "4") (pinfunction "4_4") (pintype "bidirectional"))
    )
    (net (code "75") (name "unconnected-(MSP101-Pad5)") (class "Default")
      (node (ref "MSP101") (pin "5") (pinfunction "5_5") (pintype "bidirectional"))
    )
    (net (code "76") (name "unconnected-(MSP101-Pad6)") (class "Default")
      (node (ref "MSP101") (pin "6") (pinfunction "6_6") (pintype "bidirectional"))
    )
    (net (code "77") (name "unconnected-(MSP101-Pad7)") (class "Default")
      (node (ref "MSP101") (pin "7") (pinfunction "7_7") (pintype "bidirectional"))
    )
    (net (code "78") (name "unconnected-(MSP101-Pad8)") (class "Default")
      (node (ref "MSP101") (pin "8") (pinfunction "8_8") (pintype "bidirectional"))
    )
    (net (code "79") (name "unconnected-(MSP101-Pad10)") (class "Default")
      (node (ref "MSP101") (pin "10") (pinfunction "10_10") (pintype "bidirectional"))
    )
    (net (code "80") (name "unconnected-(MSP101-Pad12)") (class "Default")
      (node (ref "MSP101") (pin "12") (pinfunction "12_12") (pintype "bidirectional"))
    )
    (net (code "81") (name "unconnected-(MSP101-Pad13)") (class "Default")
      (node (ref "MSP101") (pin "13") (pinfunction "13_13") (pintype "bidirectional"))
    )
    (net (code "82") (name "unconnected-(MSP101-Pad18)") (class "Default")
      (node (ref "MSP101") (pin "18") (pinfunction "18_18") (pintype "bidirectional"))
    )
    (net (code "83") (name "unconnected-(MSP101-Pad19)") (class "Default")
      (node (ref "MSP101") (pin "19") (pinfunction "19_19") (pintype "bidirectional"))
    )
    (net (code "84") (name "unconnected-(MSP101-Pad22)") (class "Default")
      (node (ref "MSP101") (pin "22") (pinfunction "22_22") (pintype "bidirectional"))
    )
    (net (code "85") (name "unconnected-(MSP101-Pad23)") (class "Default")
      (node (ref "MSP101") (pin "23") (pinfunction "23_23") (pintype "bidirectional"))
    )
    (net (code "86") (name "unconnected-(MSP101-Pad24)") (class "Default")
      (node (ref "MSP101") (pin "24") (pinfunction "24_24") (pintype "bidirectional"))
    )
    (net (code "87") (name "unconnected-(MSP101-Pad25)") (class "Default")
      (node (ref "MSP101") (pin "25") (pinfunction "25_25") (pintype "bidirectional"))
    )
    (net (code "88") (name "unconnected-(MSP101-Pad26)") (class "Default")
      (node (ref "MSP101") (pin "26") (pinfunction "26_26") (pintype "bidirectional"))
    )
    (net (code "89") (name "unconnected-(MSP101-Pad27)") (class "Default")
      (node (ref "MSP101") (pin "27") (pinfunction "27_27") (pintype "bidirectional"))
    )
    (net (code "90") (name "unconnected-(MSP101-Pad28)") (class "Default")
      (node (ref "MSP101") (pin "28") (pinfunction "28_28") (pintype "bidirectional"))
    )
    (net (code "91") (name "unconnected-(MSP101-Pad29)") (class "Default")
      (node (ref "MSP101") (pin "29") (pinfunction "29_29") (pintype "bidirectional"))
    )
    (net (code "92") (name "unconnected-(MSP101-Pad30)") (class "Default")
      (node (ref "MSP101") (pin "30") (pinfunction "30_30") (pintype "bidirectional"))
    )
    (net (code "93") (name "unconnected-(MSP101-Pad31)") (class "Default")
      (node (ref "MSP101") (pin "31") (pinfunction "31_31") (pintype "bidirectional"))
    )
    (net (code "94") (name "unconnected-(MSP101-Pad32)") (class "Default")
      (node (ref "MSP101") (pin "32") (pinfunction "32_32") (pintype "bidirectional"))
    )
    (net (code "95") (name "unconnected-(MSP101-Pad33)") (class "Default")
      (node (ref "MSP101") (pin "33") (pinfunction "33_33") (pintype "bidirectional"))
    )
    (net (code "96") (name "unconnected-(MSP101-Pad34)") (class "Default")
      (node (ref "MSP101") (pin "34") (pinfunction "34_34") (pintype "bidirectional"))
    )
    (net (code "97") (name "unconnected-(MSP101-Pad35)") (class "Default")
      (node (ref "MSP101") (pin "35") (pinfunction "35_35") (pintype "bidirectional"))
    )
    (net (code "98") (name "unconnected-(MSP101-Pad36)") (class "Default")
      (node (ref "MSP101") (pin "36") (pinfunction "36_36") (pintype "bidirectional"))
    )
    (net (code "99") (name "unconnected-(MSP101-Pad41)") (class "Default")
      (node (ref "MSP101") (pin "41") (pinfunction "41_41") (pintype "bidirectional"))
    )
    (net (code "100") (name "unconnected-(MSP101-Pad42)") (class "Default")
      (node (ref "MSP101") (pin "42") (pinfunction "42_42") (pintype "bidirectional"))
    )
    (net (code "101") (name "unconnected-(MSP101-Pad45)") (class "Default")
      (node (ref "MSP101") (pin "45") (pinfunction "45_45") (pintype "bidirectional"))
    )
    (net (code "102") (name "unconnected-(MSP101-Pad46)") (class "Default")
      (node (ref "MSP101") (pin "46") (pinfunction "46_46") (pintype "bidirectional"))
    )
    (net (code "103") (name "unconnected-(MSP101-Pad47)") (class "Default")
      (node (ref "MSP101") (pin "47") (pinfunction "47_47") (pintype "bidirectional"))
    )
    (net (code "104") (name "unconnected-(MSP101-Pad48)") (class "Default")
      (node (ref "MSP101") (pin "48") (pinfunction "48_48") (pintype "bidirectional"))
    )
    (net (code "105") (name "unconnected-(U$4-Pad1)") (class "Default")
      (node (ref "U$4") (pin "1") (pinfunction "1_1") (pintype "bidirectional"))
    )
    (net (code "106") (name "unconnected-(U$4-Pad8)") (class "Default")
      (node (ref "U$4") (pin "8") (pinfunction "8_8") (pintype "bidirectional"))
    )
    (net (code "107") (name "unconnected-(U$4-Pad10)") (class "Default")
      (node (ref "U$4") (pin "10") (pinfunction "10_10") (pintype "bidirectional"))
    )
    (net (code "108") (name "unconnected-(U$4-Pad12)") (class "Default")
      (node (ref "U$4") (pin "12") (pinfunction "12_12") (pintype "bidirectional"))
    )
    (net (code "109") (name "unconnected-(U$4-Pad13)") (class "Default")
      (node (ref "U$4") (pin "13") (pinfunction "13_13") (pintype "bidirectional"))
    )
    (net (code "110") (name "unconnected-(U$4-Pad14)") (class "Default")
      (node (ref "U$4") (pin "14") (pinfunction "14_14") (pintype "bidirectional"))
    )
    (net (code "111") (name "unconnected-(U$4-Pad15)") (class "Default")
      (node (ref "U$4") (pin "15") (pinfunction "15_15") (pintype "bidirectional"))
    )
    (net (code "112") (name "unconnected-(U$4-Pad16)") (class "Default")
      (node (ref "U$4") (pin "16") (pinfunction "16_16") (pintype "bidirectional"))
    )
    (net (code "113") (name "unconnected-(U$4-Pad17)") (class "Default")
      (node (ref "U$4") (pin "17") (pinfunction "17_17") (pintype "bidirectional"))
    )
    (net (code "114") (name "unconnected-(U$4-Pad18)") (class "Default")
      (node (ref "U$4") (pin "18") (pinfunction "18_18") (pintype "bidirectional"))
    )
    (net (code "115") (name "unconnected-(U$4-Pad19)") (class "Default")
      (node (ref "U$4") (pin "19") (pinfunction "19_19") (pintype "bidirectional"))
    )
    (net (code "116") (name "unconnected-(U$4-Pad35)") (class "Default")
      (node (ref "U$4") (pin "35") (pinfunction "35_35") (pintype "bidirectional"))
    )
    (net (code "117") (name "unconnected-(U$4-Pad38)") (class "Default")
      (node (ref "U$4") (pin "38") (pinfunction "38_38") (pintype "bidirectional"))
    )
    (net (code "118") (name "unconnected-(U$4-Pad39)") (class "Default")
      (node (ref "U$4") (pin "39") (pinfunction "39_39") (pintype "bidirectional"))
    )
    (net (code "119") (name "unconnected-(U$4-Pad40)") (class "Default")
      (node (ref "U$4") (pin "40") (pinfunction "40_40") (pintype "bidirectional"))
    )
    (net (code "120") (name "unconnected-(U$4-Pad42)") (class "Default")
      (node (ref "U$4") (pin "42") (pinfunction "42_42") (pintype "bidirectional"))
    )
    (net (code "121") (name "unconnected-(U$4-Pad43)") (class "Default")
      (node (ref "U$4") (pin "43") (pinfunction "43_43") (pintype "bidirectional"))
    )
    (net (code "122") (name "unconnected-(U1-P4-Pad4)") (class "Default")
      (node (ref "U1") (pin "4") (pinfunction "P4_4") (pintype "bidirectional"))
    )
    (net (code "123") (name "unconnected-(U2-P4-Pad4)") (class "Default")
      (node (ref "U2") (pin "4") (pinfunction "P4_4") (pintype "bidirectional"))
    )
    (net (code "124") (name "unconnected-(USB1-PadNC)") (class "Default")
      (node (ref "USB1") (pin "NC") (pinfunction "NC_NC") (pintype "input"))
    )
  )
)
